# Adafruit_AT42QT1070_Breakout.net
KiCad netlist of a schematic drawn in EAGLE
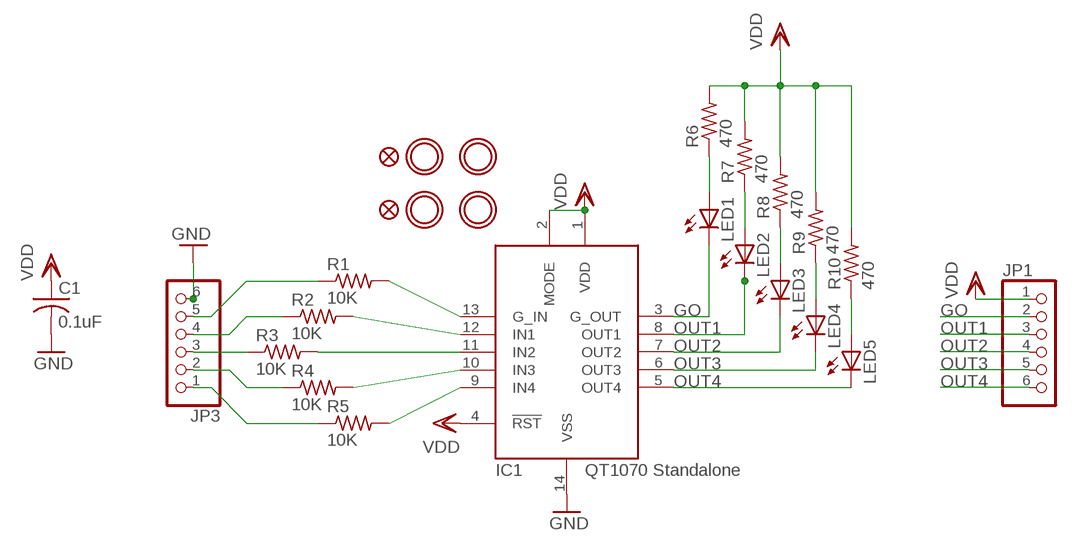
[diagram p0: schematic, sheet 1]

(export (version "E")
  (design (tool "Eeschema 10.0.6"))
  (components
    (comp (ref "C1")
      (value "0.1uF")
      (footprint "eagle-import:C0805K")
      (libsource (lib "eagle-import") (part "C-USC0805K"))
    )
    (comp (ref "FID1")
      (value "FIDUCIAL\"\"")
      (footprint "eagle-import:FIDUCIAL_1MM")
      (libsource (lib "eagle-import") (part "FIDUCIAL{dblquote}{dblquote}"))
    )
    (comp (ref "FID2")
      (value "FIDUCIAL\"\"")
      (footprint "eagle-import:FIDUCIAL_1MM")
      (libsource (lib "eagle-import") (part "FIDUCIAL{dblquote}{dblquote}"))
    )
    (comp (ref "IC1")
      (value "AT42QT1070-SSU")
      (footprint "eagle-import:SO14")
      (libsource (lib "eagle-import") (part "AT42QT1070-SSU"))
    )
    (comp (ref "JP1")
      (value "PINHD-1X6CB")
      (footprint "eagle-import:1X06-CLEANBIG")
      (libsource (lib "eagle-import") (part "PINHD-1X6CB"))
    )
    (comp (ref "JP3")
      (value "PINHD-1X6CB")
      (footprint "eagle-import:1X06-CLEANBIG")
      (libsource (lib "eagle-import") (part "PINHD-1X6CB"))
    )
    (comp (ref "LED1")
      (value "LEDCHIP-LED0805")
      (footprint "eagle-import:CHIP-LED0805")
      (libsource (lib "eagle-import") (part "LEDCHIP-LED0805"))
    )
    (comp (ref "LED2")
      (value "LEDCHIP-LED0805")
      (footprint "eagle-import:CHIP-LED0805")
      (libsource (lib "eagle-import") (part "LEDCHIP-LED0805"))
    )
    (comp (ref "LED3")
      (value "LEDCHIP-LED0805")
      (footprint "eagle-import:CHIP-LED0805")
      (libsource (lib "eagle-import") (part "LEDCHIP-LED0805"))
    )
    (comp (ref "LED4")
      (value "LEDCHIP-LED0805")
      (footprint "eagle-import:CHIP-LED0805")
      (libsource (lib "eagle-import") (part "LEDCHIP-LED0805"))
    )
    (comp (ref "LED5")
      (value "LEDCHIP-LED0805")
      (footprint "eagle-import:CHIP-LED0805")
      (libsource (lib "eagle-import") (part "LEDCHIP-LED0805"))
    )
    (comp (ref "R1")
      (value "10K")
      (footprint "eagle-import:R0805")
      (libsource (lib "eagle-import") (part "R-US_R0805"))
    )
    (comp (ref "R2")
      (value "10K")
      (footprint "eagle-import:R0805")
      (libsource (lib "eagle-import") (part "R-US_R0805"))
    )
    (comp (ref "R3")
      (value "10K")
      (footprint "eagle-import:R0805")
      (libsource (lib "eagle-import") (part "R-US_R0805"))
    )
    (comp (ref "R4")
      (value "10K")
      (footprint "eagle-import:R0805")
      (libsource (lib "eagle-import") (part "R-US_R0805"))
    )
    (comp (ref "R5")
      (value "10K")
      (footprint "eagle-import:R0805")
      (libsource (lib "eagle-import") (part "R-US_R0805"))
    )
    (comp (ref "R6")
      (value "470")
      (footprint "eagle-import:R0805")
      (libsource (lib "eagle-import") (part "R-US_R0805"))
    )
    (comp (ref "R7")
      (value "470")
      (footprint "eagle-import:R0805")
      (libsource (lib "eagle-import") (part "R-US_R0805"))
    )
    (comp (ref "R8")
      (value "470")
      (footprint "eagle-import:R0805")
      (libsource (lib "eagle-import") (part "R-US_R0805"))
    )
    (comp (ref "R9")
      (value "470")
      (footprint "eagle-import:R0805")
      (libsource (lib "eagle-import") (part "R-US_R0805"))
    )
    (comp (ref "R10")
      (value "470")
      (footprint "eagle-import:R0805")
      (libsource (lib "eagle-import") (part "R-US_R0805"))
    )
    (comp (ref "U$1")
      (value "MOUNTINGHOLE2.5")
      (footprint "eagle-import:MOUNTINGHOLE_2.5_PLATED")
      (libsource (lib "eagle-import") (part "MOUNTINGHOLE2.5"))
    )
    (comp (ref "U$2")
      (value "MOUNTINGHOLE2.5")
      (footprint "eagle-import:MOUNTINGHOLE_2.5_PLATED")
      (libsource (lib "eagle-import") (part "MOUNTINGHOLE2.5"))
    )
    (comp (ref "U$3")
      (value "MOUNTINGHOLE2.5")
      (footprint "eagle-import:MOUNTINGHOLE_2.5_PLATED")
      (libsource (lib "eagle-import") (part "MOUNTINGHOLE2.5"))
    )
    (comp (ref "U$4")
      (value "MOUNTINGHOLE2.5")
      (footprint "eagle-import:MOUNTINGHOLE_2.5_PLATED")
      (libsource (lib "eagle-import") (part "MOUNTINGHOLE2.5"))
    )
  )
  (nets
    (net (code "1") (name "/GO") (class "Default")
      (node (ref "IC1") (pin "3") (pinfunction "G_OUT_3") (pintype "open_collector"))
      (node (ref "JP1") (pin "2") (pinfunction "2_2") (pintype "passive"))
      (node (ref "LED1") (pin "C") (pinfunction "C_C") (pintype "passive"))
    )
    (net (code "2") (name "/OUT1") (class "Default")
      (node (ref "IC1") (pin "8") (pinfunction "OUT1_8") (pintype "open_collector"))
      (node (ref "JP1") (pin "3") (pinfunction "3_3") (pintype "passive"))
      (node (ref "LED2") (pin "C") (pinfunction "C_C") (pintype "passive"))
    )
    (net (code "3") (name "/OUT2") (class "Default")
      (node (ref "IC1") (pin "7") (pinfunction "OUT2_7") (pintype "open_collector"))
      (node (ref "JP1") (pin "4") (pinfunction "4_4") (pintype "passive"))
      (node (ref "LED3") (pin "C") (pinfunction "C_C") (pintype "passive"))
    )
    (net (code "4") (name "/OUT3") (class "Default")
      (node (ref "IC1") (pin "6") (pinfunction "OUT3_6") (pintype "open_collector"))
      (node (ref "JP1") (pin "5") (pinfunction "5_5") (pintype "passive"))
      (node (ref "LED4") (pin "C") (pinfunction "C_C") (pintype "passive"))
    )
    (net (code "5") (name "/OUT4") (class "Default")
      (node (ref "IC1") (pin "5") (pinfunction "OUT4_5") (pintype "open_collector"))
      (node (ref "JP1") (pin "6") (pinfunction "6_6") (pintype "passive"))
      (node (ref "LED5") (pin "C") (pinfunction "C_C") (pintype "passive"))
    )
    (net (code "6") (name "GND") (class "Default")
      (node (ref "C1") (pin "2") (pinfunction "2_2") (pintype "passive"))
      (node (ref "IC1") (pin "14") (pinfunction "VSS_14") (pintype "power_in"))
      (node (ref "JP3") (pin "6") (pinfunction "6_6") (pintype "passive"))
    )
    (net (code "7") (name "Net-(IC1-G_IN)") (class "Default")
      (node (ref "IC1") (pin "13") (pinfunction "G_IN_13") (pintype "input"))
      (node (ref "R1") (pin "2") (pinfunction "2_2") (pintype "passive"))
    )
    (net (code "8") (name "Net-(IC1-IN1)") (class "Default")
      (node (ref "IC1") (pin "12") (pinfunction "IN1_12") (pintype "input"))
      (node (ref "R2") (pin "2") (pinfunction "2_2") (pintype "passive"))
    )
    (net (code "9") (name "Net-(IC1-IN2)") (class "Default")
      (node (ref "IC1") (pin "11") (pinfunction "IN2_11") (pintype "input"))
      (node (ref "R3") (pin "2") (pinfunction "2_2") (pintype "passive"))
    )
    (net (code "10") (name "Net-(IC1-IN3)") (class "Default")
      (node (ref "IC1") (pin "10") (pinfunction "IN3_10") (pintype "input"))
      (node (ref "R4") (pin "2") (pinfunction "2_2") (pintype "passive"))
    )
    (net (code "11") (name "Net-(IC1-IN4)") (class "Default")
      (node (ref "IC1") (pin "9") (pinfunction "IN4_9") (pintype "input"))
      (node (ref "R5") (pin "2") (pinfunction "2_2") (pintype "passive"))
    )
    (net (code "12") (name "Net-(JP3-Pad1)") (class "Default")
      (node (ref "JP3") (pin "1") (pinfunction "1_1") (pintype "passive"))
      (node (ref "R5") (pin "1") (pinfunction "1_1") (pintype "passive"))
    )
    (net (code "13") (name "Net-(JP3-Pad2)") (class "Default")
      (node (ref "JP3") (pin "2") (pinfunction "2_2") (pintype "passive"))
      (node (ref "R4") (pin "1") (pinfunction "1_1") (pintype "passive"))
    )
    (net (code "14") (name "Net-(JP3-Pad3)") (class "Default")
      (node (ref "JP3") (pin "3") (pinfunction "3_3") (pintype "passive"))
      (node (ref "R3") (pin "1") (pinfunction "1_1") (pintype "passive"))
    )
    (net (code "15") (name "Net-(JP3-Pad4)") (class "Default")
      (node (ref "JP3") (pin "4") (pinfunction "4_4") (pintype "passive"))
      (node (ref "R2") (pin "1") (pinfunction "1_1") (pintype "passive"))
    )
    (net (code "16") (name "Net-(JP3-Pad5)") (class "Default")
      (node (ref "JP3") (pin "5") (pinfunction "5_5") (pintype "passive"))
      (node (ref "R1") (pin "1") (pinfunction "1_1") (pintype "passive"))
    )
    (net (code "17") (name "Net-(LED1-PadA)") (class "Default")
      (node (ref "LED1") (pin "A") (pinfunction "A_A") (pintype "passive"))
      (node (ref "R6") (pin "1") (pinfunction "1_1") (pintype "passive"))
    )
    (net (code "18") (name "Net-(LED2-PadA)") (class "Default")
      (node (ref "LED2") (pin "A") (pinfunction "A_A") (pintype "passive"))
      (node (ref "R7") (pin "1") (pinfunction "1_1") (pintype "passive"))
    )
    (net (code "19") (name "Net-(LED3-PadA)") (class "Default")
      (node (ref "LED3") (pin "A") (pinfunction "A_A") (pintype "passive"))
      (node (ref "R8") (pin "1") (pinfunction "1_1") (pintype "passive"))
    )
    (net (code "20") (name "Net-(LED4-PadA)") (class "Default")
      (node (ref "LED4") (pin "A") (pinfunction "A_A") (pintype "passive"))
      (node (ref "R9") (pin "1") (pinfunction "1_1") (pintype "passive"))
    )
    (net (code "21") (name "Net-(LED5-PadA)") (class "Default")
      (node (ref "LED5") (pin "A") (pinfunction "A_A") (pintype "passive"))
      (node (ref "R10") (pin "1") (pinfunction "1_1") (pintype "passive"))
    )
    (net (code "22") (name "VDD") (class "Default")
      (node (ref "C1") (pin "1") (pinfunction "1_1") (pintype "passive"))
      (node (ref "IC1") (pin "1") (pinfunction "VDD_1") (pintype "power_in"))
      (node (ref "IC1") (pin "2") (pinfunction "MODE_2") (pintype "input"))
      (node (ref "IC1") (pin "4") (pinfunction "~{RST}_4") (pintype "input"))
      (node (ref "JP1") (pin "1") (pinfunction "1_1") (pintype "passive"))
      (node (ref "R10") (pin "2") (pinfunction "2_2") (pintype "passive"))
      (node (ref "R6") (pin "2") (pinfunction "2_2") (pintype "passive"))
      (node (ref "R7") (pin "2") (pinfunction "2_2") (pintype "passive"))
      (node (ref "R8") (pin "2") (pinfunction "2_2") (pintype "passive"))
      (node (ref "R9") (pin "2") (pinfunction "2_2") (pintype "passive"))
    )
  )
)
